# POWER_MCU.net
KiCad netlist of a schematic drawn in Altium Designer
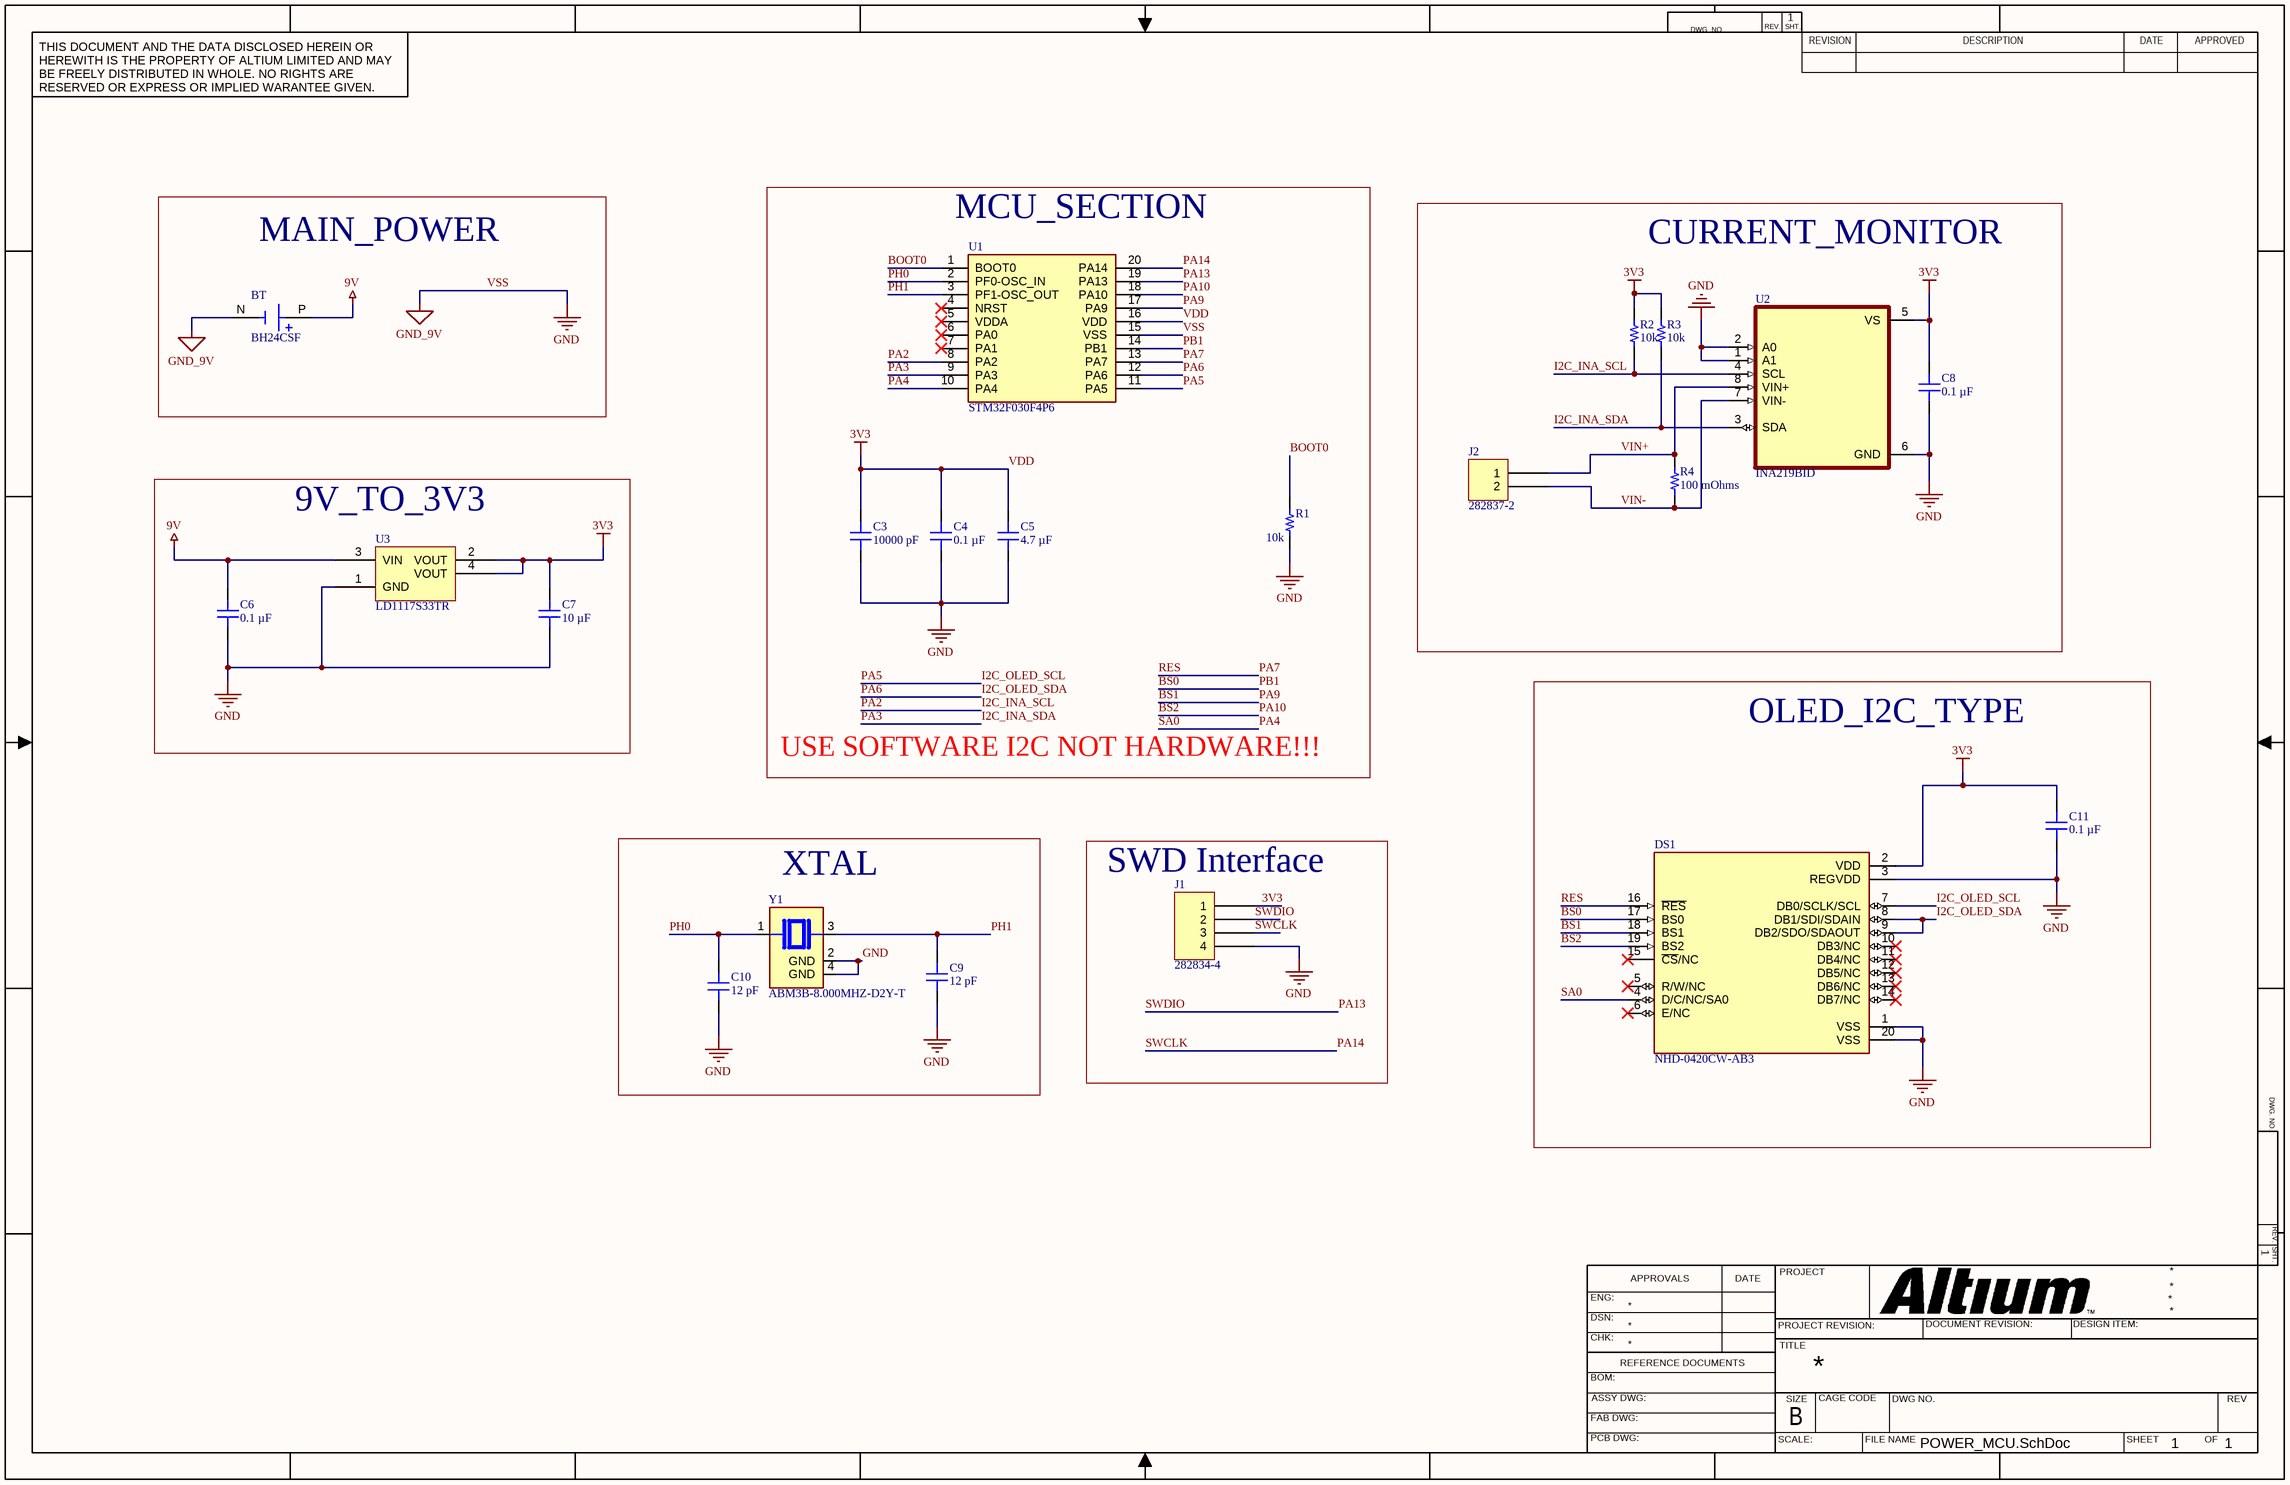
[diagram p0: POWER_MCU.SchDoc]

(export (version "E")
  (design (tool "Eeschema 10.0.6"))
  (components
    (comp (ref "BT")
      (value "BH24CSF")
      (footprint "BAT_BH24CSF")
      (description "BATTERY HOLDER C 4 CELL 9V SNAP")
      (fields (field (name "MF") "MPD"))
      (libsource (lib "MyAltLib") (part "BH24CSF"))
    )
    (comp (ref "C3")
      (value "10000 pF")
      (footprint "CAP 0805_2012")
      (description "CAP CER 0805 10NF 100V X7R")
      (fields
        (field (name "PART NUMBER") "C0805X103K1RAC3316")
        (field (name "CAPACITANCE") "10000 pF")
        (field (name "MANUFACTURER") "KEMET")
      )
      (libsource (lib "Celestial Altium Library - altium_library") (part "Capacitor"))
    )
    (comp (ref "C4")
      (value "0.1 µF")
      (footprint "CAP 0805_2012")
      (description "CAP CER 0.1UF 50V X7R 0805")
      (fields
        (field (name "PART NUMBER") "C0805C104M5RACAUTO")
        (field (name "CAPACITANCE") "0.1 µF")
        (field (name "MANUFACTURER") "KEMET")
      )
      (libsource (lib "Celestial Altium Library - altium_library") (part "Capacitor"))
    )
    (comp (ref "C5")
      (value "4.7 µF")
      (footprint "CAP 0805_2012")
      (description "CAP CER 4.7UF 6.3V X7R 0805")
      (fields
        (field (name "PART NUMBER") "C0805X475J9RACAUTO")
        (field (name "CAPACITANCE") "4.7 µF")
        (field (name "MANUFACTURER") "KEMET")
      )
      (libsource (lib "Celestial Altium Library - altium_library") (part "Capacitor"))
    )
    (comp (ref "C6")
      (value "0.1 µF")
      (footprint "CAP 0805_2012")
      (description "CAP CER 0.1UF 50V X7R 0805")
      (fields
        (field (name "PART NUMBER") "C0805C104M5RACAUTO")
        (field (name "CAPACITANCE") "0.1 µF")
        (field (name "MANUFACTURER") "KEMET")
      )
      (libsource (lib "Celestial Altium Library - altium_library") (part "Capacitor"))
    )
    (comp (ref "C7")
      (value "10 µF")
      (footprint "CAP 0805_2012")
      (description "CAP CER 10UF 10V X7S 0805")
      (fields
        (field (name "PART NUMBER") "CL21Y106KPQVPNE")
        (field (name "CAPACITANCE") "10 µF")
        (field (name "MANUFACTURER") "Samsung Electro-Mechanics")
      )
      (libsource (lib "Celestial Altium Library - altium_library") (part "Capacitor"))
    )
    (comp (ref "C8")
      (value "0.1 µF")
      (footprint "CAP 0805_2012")
      (description "CAP CER 0.1UF 50V X7R 0805")
      (fields
        (field (name "PART NUMBER") "C0805C104M5RACAUTO")
        (field (name "CAPACITANCE") "0.1 µF")
        (field (name "MANUFACTURER") "KEMET")
      )
      (libsource (lib "Celestial Altium Library - altium_library") (part "Capacitor"))
    )
    (comp (ref "C9")
      (value "12 pF")
      (footprint "CAP 0402_1005")
      (description "CAP CER 12PF 50V C0G/NP0 0402")
      (fields
        (field (name "PART NUMBER") "CBR04C120F5GAC")
        (field (name "CAPACITANCE") "12 pF")
        (field (name "MANUFACTURER") "KEMET")
      )
      (libsource (lib "Celestial Altium Library - altium_library") (part "Capacitor"))
    )
    (comp (ref "C10")
      (value "12 pF")
      (footprint "CAP 0402_1005")
      (description "CAP CER 12PF 50V C0G/NP0 0402")
      (fields
        (field (name "PART NUMBER") "CBR04C120F5GAC")
        (field (name "CAPACITANCE") "12 pF")
        (field (name "MANUFACTURER") "KEMET")
      )
      (libsource (lib "Celestial Altium Library - altium_library") (part "Capacitor"))
    )
    (comp (ref "C11")
      (value "0.1 µF")
      (footprint "CAP 0805_2012")
      (description "CAP CER 0.1UF 50V X7R 0805")
      (fields
        (field (name "PART NUMBER") "C0805C104M5RACAUTO")
        (field (name "CAPACITANCE") "0.1 µF")
        (field (name "MANUFACTURER") "KEMET")
      )
      (libsource (lib "Celestial Altium Library - altium_library") (part "Capacitor"))
    )
    (comp (ref "DS1")
      (value "NHD-0420CW-AB3")
      (footprint "LCD_NHD-0420CW-AB3")
      (fields (field (name "MF") "Newhaven Display"))
      (libsource (lib "MyAltLib") (part "NHD-0420CW-AB3"))
    )
    (comp (ref "J1")
      (value "282834-4")
      (footprint "TE 282834-4")
      (description "TERM BLK 4P SIDE ENT 2.54MM PCB")
      (fields (field (name "MANUFACTURER") "TE Connectivity AMP Connectors") (field (name "VOLTAGE") "150V"))
      (libsource (lib "Celestial Altium Library - altium_library") (part "4 Pin"))
    )
    (comp (ref "J2")
      (value "282837-2")
      (footprint "TE 282837-2")
      (description "TERM BLK 2P SIDE ENT 5.08MM PCB")
      (fields (field (name "MANUFACTURER") "TE Connectivity AMP Connectors") (field (name "VOLTAGE") "300 V"))
      (libsource (lib "Celestial Altium Library - altium_library") (part "2 Pin"))
    )
    (comp (ref "R1")
      (value "10k Ohms")
      (footprint "RES 0805_2012")
      (description "RES 0 OHM JUMPER 0805")
      (fields
        (field (name "PART NUMBER") "TLRZ2ATTD")
        (field (name "MANUFACTURER") "KOA Speer Electronics, Inc.")
      )
      (libsource (lib "Celestial Altium Library - altium_library") (part "Resistor"))
    )
    (comp (ref "R2")
      (value "10k")
      (footprint "RES 0805_2012")
      (description "RES 10K OHM 0.1% 1/10W 0805")
      (fields
        (field (name "PART NUMBER") "RNCS0805BKE10K0")
        (field (name "MANUFACTURER") "Stackpole Electronics Inc")
      )
      (libsource (lib "Celestial Altium Library - altium_library") (part "Resistor"))
    )
    (comp (ref "R3")
      (value "10k")
      (footprint "RES 0805_2012")
      (description "RES 10K OHM 0.1% 1/10W 0805")
      (fields
        (field (name "PART NUMBER") "RNCS0805BKE10K0")
        (field (name "MANUFACTURER") "Stackpole Electronics Inc")
      )
      (libsource (lib "Celestial Altium Library - altium_library") (part "Resistor"))
    )
    (comp (ref "R4")
      (value "100 mOhms")
      (footprint "RES 2512_6432")
      (description "RES 0.1 OHM 1% 2W 2512")
      (fields
        (field (name "PART NUMBER") "CSRF2512FTR100")
        (field (name "MANUFACTURER") "Stackpole Electronics Inc")
      )
      (libsource (lib "Celestial Altium Library - altium_library") (part "Resistor"))
    )
    (comp (ref "U1")
      (value "STM32F030F4P6")
      (footprint "TSSOP-20")
      (fields (field (name "MOUSER PART NUMBER") "511-STM32F030F4P6"))
      (libsource (lib "MyAltLib") (part "STM32F030F4P6"))
    )
    (comp (ref "U2")
      (value "INA219BID")
      (footprint "SOIC-8")
      (description "26V, 12-bit, i2c output current/voltage/power monitor")
      (fields (field (name "MF") "Texas Instruments"))
      (libsource (lib "MyAltLib") (part "INA219BID"))
    )
    (comp (ref "U3")
      (value "LD1117S33TR")
      (footprint "ST SOT-223")
      (description "IC REG LINEAR 3.3V 800MA SOT223")
      (fields (field (name "MANUFACTURER") "STMicroelectronics"))
      (libsource (lib "Celestial Altium Library - altium_library") (part "ST LD1117"))
    )
    (comp (ref "Y1")
      (value "ABM3B-8.000MHZ-D2Y-T")
      (footprint "XTAL_ABM3B-8.000MHZ-D2Y-T")
      (description "Crystal 8MHz Â±20ppm (Tol) Â±30ppm (Stability) 18pF FUND 200Ohm 4-Pin CSMD T/R")
      (fields (field (name "MF") "Abracon LLC"))
      (libsource (lib "MyAltLib") (part "ABM3B-8.000MHZ-D2Y-T"))
    )
  )
  (nets
    (net (code "2") (name "/BOOT0") (class "Default")
      (node (ref "R1") (pin "2") (pinfunction "2_2") (pintype "passive"))
      (node (ref "U1") (pin "1") (pinfunction "BOOT0_1") (pintype "passive"))
    )
    (net (code "3") (name "/BS0") (class "Default")
      (node (ref "DS1") (pin "17") (pinfunction "BS0_17") (pintype "input"))
      (node (ref "U1") (pin "14") (pinfunction "PB1_14") (pintype "passive"))
    )
    (net (code "4") (name "/BS1") (class "Default")
      (node (ref "DS1") (pin "18") (pinfunction "BS1_18") (pintype "input"))
      (node (ref "U1") (pin "17") (pinfunction "PA9_17") (pintype "passive"))
    )
    (net (code "5") (name "/BS2") (class "Default")
      (node (ref "DS1") (pin "19") (pinfunction "BS2_19") (pintype "input"))
      (node (ref "U1") (pin "18") (pinfunction "PA10_18") (pintype "passive"))
    )
    (net (code "6") (name "/I2C_INA_SCL") (class "Default")
      (node (ref "R2") (pin "1") (pinfunction "1_1") (pintype "passive"))
      (node (ref "U1") (pin "8") (pinfunction "PA2_8") (pintype "passive"))
      (node (ref "U2") (pin "4") (pinfunction "SCL_4") (pintype "input"))
    )
    (net (code "7") (name "/I2C_INA_SDA") (class "Default")
      (node (ref "R3") (pin "1") (pinfunction "1_1") (pintype "passive"))
      (node (ref "U1") (pin "9") (pinfunction "PA3_9") (pintype "passive"))
      (node (ref "U2") (pin "3") (pinfunction "SDA_3") (pintype "bidirectional"))
    )
    (net (code "8") (name "/I2C_OLED_SCL") (class "Default")
      (node (ref "DS1") (pin "7") (pinfunction "DB0/SCLK/SCL_7") (pintype "bidirectional"))
      (node (ref "U1") (pin "11") (pinfunction "PA5_11") (pintype "passive"))
    )
    (net (code "9") (name "/I2C_OLED_SDA") (class "Default")
      (node (ref "DS1") (pin "8") (pinfunction "DB1/SDI/SDAIN_8") (pintype "bidirectional"))
      (node (ref "DS1") (pin "9") (pinfunction "DB2/SDO/SDAOUT_9") (pintype "bidirectional"))
      (node (ref "U1") (pin "12") (pinfunction "PA6_12") (pintype "passive"))
    )
    (net (code "10") (name "/PA4") (class "Default")
      (node (ref "DS1") (pin "4") (pinfunction "D/C/NC/SA0_4") (pintype "bidirectional"))
      (node (ref "U1") (pin "10") (pinfunction "PA4_10") (pintype "passive"))
    )
    (net (code "11") (name "/PA7") (class "Default")
      (node (ref "DS1") (pin "16") (pinfunction "~{RES}_16") (pintype "input"))
      (node (ref "U1") (pin "13") (pinfunction "PA7_13") (pintype "passive"))
    )
    (net (code "12") (name "/PA13") (class "Default")
      (node (ref "J1") (pin "2") (pinfunction "2_2") (pintype "passive"))
      (node (ref "U1") (pin "19") (pinfunction "PA13_19") (pintype "passive"))
    )
    (net (code "13") (name "/PA14") (class "Default")
      (node (ref "J1") (pin "3") (pinfunction "3_3") (pintype "passive"))
      (node (ref "U1") (pin "20") (pinfunction "PA14_20") (pintype "passive"))
    )
    (net (code "14") (name "/PH0") (class "Default")
      (node (ref "C10") (pin "2") (pinfunction "2_2") (pintype "passive"))
      (node (ref "U1") (pin "2") (pinfunction "PF0-OSC_IN_2") (pintype "passive"))
      (node (ref "Y1") (pin "1") (pinfunction "1_1") (pintype "passive"))
    )
    (net (code "15") (name "/PH1") (class "Default")
      (node (ref "C9") (pin "2") (pinfunction "2_2") (pintype "passive"))
      (node (ref "U1") (pin "3") (pinfunction "PF1-OSC_OUT_3") (pintype "passive"))
      (node (ref "Y1") (pin "3") (pinfunction "2_3") (pintype "passive"))
    )
    (net (code "16") (name "/VIN+") (class "Default")
      (node (ref "J2") (pin "1") (pinfunction "1_1") (pintype "passive"))
      (node (ref "R4") (pin "2") (pinfunction "2_2") (pintype "passive"))
      (node (ref "U2") (pin "8") (pinfunction "VIN+_8") (pintype "input"))
    )
    (net (code "17") (name "/VIN-") (class "Default")
      (node (ref "J2") (pin "2") (pinfunction "2_2") (pintype "passive"))
      (node (ref "R4") (pin "1") (pinfunction "1_1") (pintype "passive"))
      (node (ref "U2") (pin "7") (pinfunction "VIN-_7") (pintype "input"))
    )
    (net (code "18") (name "3V3") (class "Default")
      (node (ref "C11") (pin "2") (pinfunction "2_2") (pintype "passive"))
      (node (ref "C3") (pin "2") (pinfunction "2_2") (pintype "passive"))
      (node (ref "C4") (pin "2") (pinfunction "2_2") (pintype "passive"))
      (node (ref "C5") (pin "2") (pinfunction "2_2") (pintype "passive"))
      (node (ref "C7") (pin "2") (pinfunction "2_2") (pintype "passive"))
      (node (ref "C8") (pin "2") (pinfunction "2_2") (pintype "passive"))
      (node (ref "DS1") (pin "2") (pinfunction "VDD_2") (pintype "power_in"))
      (node (ref "J1") (pin "1") (pinfunction "1_1") (pintype "passive"))
      (node (ref "R2") (pin "2") (pinfunction "2_2") (pintype "passive"))
      (node (ref "R3") (pin "2") (pinfunction "2_2") (pintype "passive"))
      (node (ref "U1") (pin "16") (pinfunction "VDD_16") (pintype "passive"))
      (node (ref "U2") (pin "5") (pinfunction "VS_5") (pintype "power_in"))
      (node (ref "U3") (pin "2") (pinfunction "VOUT_2") (pintype "passive"))
      (node (ref "U3") (pin "4") (pinfunction "VOUT_4") (pintype "passive"))
    )
    (net (code "19") (name "9V") (class "Default")
      (node (ref "BT") (pin "P") (pinfunction "POS_P") (pintype "passive"))
      (node (ref "C6") (pin "2") (pinfunction "2_2") (pintype "passive"))
      (node (ref "U3") (pin "3") (pinfunction "VIN_3") (pintype "passive"))
    )
    (net (code "20") (name "GND") (class "Default")
      (node (ref "BT") (pin "N") (pinfunction "NEG_N") (pintype "passive"))
      (node (ref "C10") (pin "1") (pinfunction "1_1") (pintype "passive"))
      (node (ref "C11") (pin "1") (pinfunction "1_1") (pintype "passive"))
      (node (ref "C3") (pin "1") (pinfunction "1_1") (pintype "passive"))
      (node (ref "C4") (pin "1") (pinfunction "1_1") (pintype "passive"))
      (node (ref "C5") (pin "1") (pinfunction "1_1") (pintype "passive"))
      (node (ref "C6") (pin "1") (pinfunction "1_1") (pintype "passive"))
      (node (ref "C7") (pin "1") (pinfunction "1_1") (pintype "passive"))
      (node (ref "C8") (pin "1") (pinfunction "1_1") (pintype "passive"))
      (node (ref "C9") (pin "1") (pinfunction "1_1") (pintype "passive"))
      (node (ref "DS1") (pin "1") (pinfunction "VSS_1") (pintype "power_in"))
      (node (ref "DS1") (pin "20") (pinfunction "VSS_20") (pintype "power_in"))
      (node (ref "DS1") (pin "3") (pinfunction "REGVDD_3") (pintype "power_in"))
      (node (ref "J1") (pin "4") (pinfunction "4_4") (pintype "passive"))
      (node (ref "R1") (pin "1") (pinfunction "1_1") (pintype "passive"))
      (node (ref "U1") (pin "15") (pinfunction "VSS_15") (pintype "passive"))
      (node (ref "U2") (pin "1") (pinfunction "A1_1") (pintype "input"))
      (node (ref "U2") (pin "2") (pinfunction "A0_2") (pintype "input"))
      (node (ref "U2") (pin "6") (pinfunction "GND_6") (pintype "power_in"))
      (node (ref "U3") (pin "1") (pinfunction "GND_1") (pintype "passive"))
      (node (ref "Y1") (pin "2") (pinfunction "GND_2") (pintype "power_in"))
      (node (ref "Y1") (pin "4") (pinfunction "GND_4") (pintype "power_in"))
    )
    (net (code "21") (name "unconnected-(DS1-DB3{slash}NC-Pad10)") (class "Default")
      (node (ref "DS1") (pin "10") (pinfunction "DB3/NC_10") (pintype "bidirectional+no_connect"))
    )
    (net (code "22") (name "unconnected-(DS1-DB4{slash}NC-Pad11)") (class "Default")
      (node (ref "DS1") (pin "11") (pinfunction "DB4/NC_11") (pintype "bidirectional+no_connect"))
    )
    (net (code "23") (name "unconnected-(DS1-DB5{slash}NC-Pad12)") (class "Default")
      (node (ref "DS1") (pin "12") (pinfunction "DB5/NC_12") (pintype "bidirectional+no_connect"))
    )
    (net (code "24") (name "unconnected-(DS1-DB6{slash}NC-Pad13)") (class "Default")
      (node (ref "DS1") (pin "13") (pinfunction "DB6/NC_13") (pintype "bidirectional+no_connect"))
    )
    (net (code "25") (name "unconnected-(DS1-DB7{slash}NC-Pad14)") (class "Default")
      (node (ref "DS1") (pin "14") (pinfunction "DB7/NC_14") (pintype "bidirectional+no_connect"))
    )
    (net (code "26") (name "unconnected-(DS1-E{slash}NC-Pad6)") (class "Default")
      (node (ref "DS1") (pin "6") (pinfunction "E/NC_6") (pintype "bidirectional+no_connect"))
    )
    (net (code "27") (name "unconnected-(DS1-R{slash}W{slash}NC-Pad5)") (class "Default")
      (node (ref "DS1") (pin "5") (pinfunction "R/W/NC_5") (pintype "bidirectional+no_connect"))
    )
    (net (code "28") (name "unconnected-(DS1-~{CS}{slash}NC-Pad15)") (class "Default")
      (node (ref "DS1") (pin "15") (pinfunction "~{CS}/NC_15") (pintype "passive+no_connect"))
    )
    (net (code "29") (name "unconnected-(U1-NRST-Pad4)") (class "Default")
      (node (ref "U1") (pin "4") (pinfunction "NRST_4") (pintype "passive+no_connect"))
    )
    (net (code "30") (name "unconnected-(U1-PA0-Pad6)") (class "Default")
      (node (ref "U1") (pin "6") (pinfunction "PA0_6") (pintype "passive+no_connect"))
    )
    (net (code "31") (name "unconnected-(U1-PA1-Pad7)") (class "Default")
      (node (ref "U1") (pin "7") (pinfunction "PA1_7") (pintype "passive+no_connect"))
    )
    (net (code "32") (name "unconnected-(U1-VDDA-Pad5)") (class "Default")
      (node (ref "U1") (pin "5") (pinfunction "VDDA_5") (pintype "passive+no_connect"))
    )
  )
)
